# Optical_SCH.net
KiCad netlist of a schematic drawn in Altium Designer
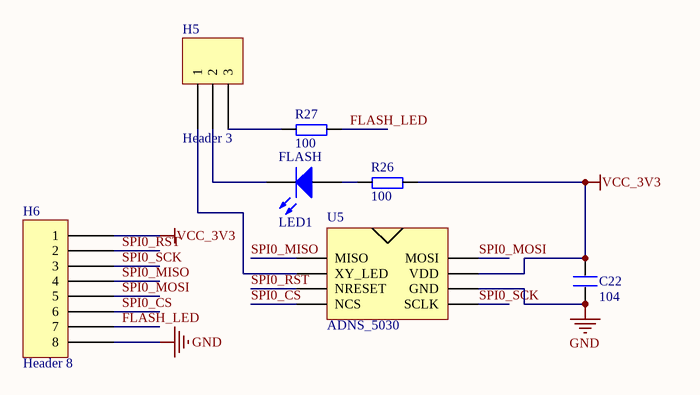
[diagram p0: Optical_SCH.SchDoc]

(export (version "E")
  (design (tool "Eeschema 10.0.6"))
  (components
    (comp (ref "C22") (value "104") (footprint "0603P") (libsource (lib "MY_SCH_Lib") (part "C")))
    (comp (ref "FLASH")
      (value "LED1")
      (footprint "LED_A2")
      (description "Typical RED, GREEN, YELLOW, AMBER GaAs LED")
      (fields (field (name "PUBLISHER") "Altium Limited"))
      (libsource (lib "MY_SCH_Lib") (part "LED2"))
    )
    (comp (ref "H5") (value "Header 3") (footprint "head3") (libsource (lib "MY_SCH_Lib") (part "Header 3")))
    (comp (ref "H6")
      (value "Header 8")
      (footprint "Header 8")
      (libsource (lib "MY_SCH_Lib") (part "Header 8"))
    )
    (comp (ref "R26") (value "100") (footprint "0603P") (libsource (lib "MY_SCH_Lib") (part "R")))
    (comp (ref "R27") (value "100") (footprint "0603P") (libsource (lib "MY_SCH_Lib") (part "R")))
    (comp (ref "U5")
      (value "ADNS_5030")
      (footprint "ADNS_5030")
      (libsource (lib "MY_SCH_Lib") (part "ADNS_5030"))
    )
  )
  (nets
    (net (code "1") (name "/FLASH_LED") (class "Default")
      (node (ref "H6") (pin "7") (pinfunction "7_7") (pintype "passive"))
      (node (ref "R27") (pin "2") (pintype "passive"))
    )
    (net (code "2") (name "/SPI0_CS") (class "Default")
      (node (ref "H6") (pin "6") (pinfunction "6_6") (pintype "passive"))
      (node (ref "U5") (pin "4") (pinfunction "NCS_4") (pintype "passive"))
    )
    (net (code "3") (name "/SPI0_MISO") (class "Default")
      (node (ref "H6") (pin "4") (pinfunction "4_4") (pintype "passive"))
      (node (ref "U5") (pin "1") (pinfunction "MISO_1") (pintype "passive"))
    )
    (net (code "4") (name "/SPI0_MOSI") (class "Default")
      (node (ref "H6") (pin "5") (pinfunction "5_5") (pintype "passive"))
      (node (ref "U5") (pin "8") (pinfunction "MOSI_8") (pintype "passive"))
    )
    (net (code "5") (name "/SPI0_RST") (class "Default")
      (node (ref "H6") (pin "2") (pinfunction "2_2") (pintype "passive"))
      (node (ref "U5") (pin "3") (pinfunction "NRESET_3") (pintype "passive"))
    )
    (net (code "6") (name "/SPI0_SCK") (class "Default")
      (node (ref "H6") (pin "3") (pinfunction "3_3") (pintype "passive"))
      (node (ref "U5") (pin "5") (pinfunction "SCLK_5") (pintype "passive"))
    )
    (net (code "7") (name "GND") (class "Default")
      (node (ref "C22") (pin "1") (pintype "passive"))
      (node (ref "H6") (pin "8") (pinfunction "8_8") (pintype "passive"))
      (node (ref "U5") (pin "6") (pinfunction "GND_6") (pintype "passive"))
    )
    (net (code "8") (name "Net-(FLASH-A)") (class "Default")
      (node (ref "FLASH") (pin "1") (pinfunction "A_1") (pintype "passive"))
      (node (ref "R26") (pin "1") (pintype "passive"))
    )
    (net (code "9") (name "Net-(FLASH-K)") (class "Default")
      (node (ref "FLASH") (pin "2") (pinfunction "K_2") (pintype "passive"))
      (node (ref "H5") (pin "2") (pinfunction "2_2") (pintype "passive"))
    )
    (net (code "10") (name "Net-(H5-Pad3)") (class "Default")
      (node (ref "H5") (pin "3") (pinfunction "3_3") (pintype "passive"))
      (node (ref "R27") (pin "1") (pintype "passive"))
    )
    (net (code "11") (name "Net-(U5-XY_LED)") (class "Default")
      (node (ref "H5") (pin "1") (pinfunction "1_1") (pintype "passive"))
      (node (ref "U5") (pin "2") (pinfunction "XY_LED_2") (pintype "passive"))
    )
    (net (code "12") (name "VCC_3V3") (class "Default")
      (node (ref "C22") (pin "2") (pintype "passive"))
      (node (ref "H6") (pin "1") (pinfunction "1_1") (pintype "passive"))
      (node (ref "R26") (pin "2") (pintype "passive"))
      (node (ref "U5") (pin "7") (pinfunction "VDD_7") (pintype "passive"))
    )
  )
)
